# Master-Module.net
KiCad netlist of a schematic drawn in EAGLE
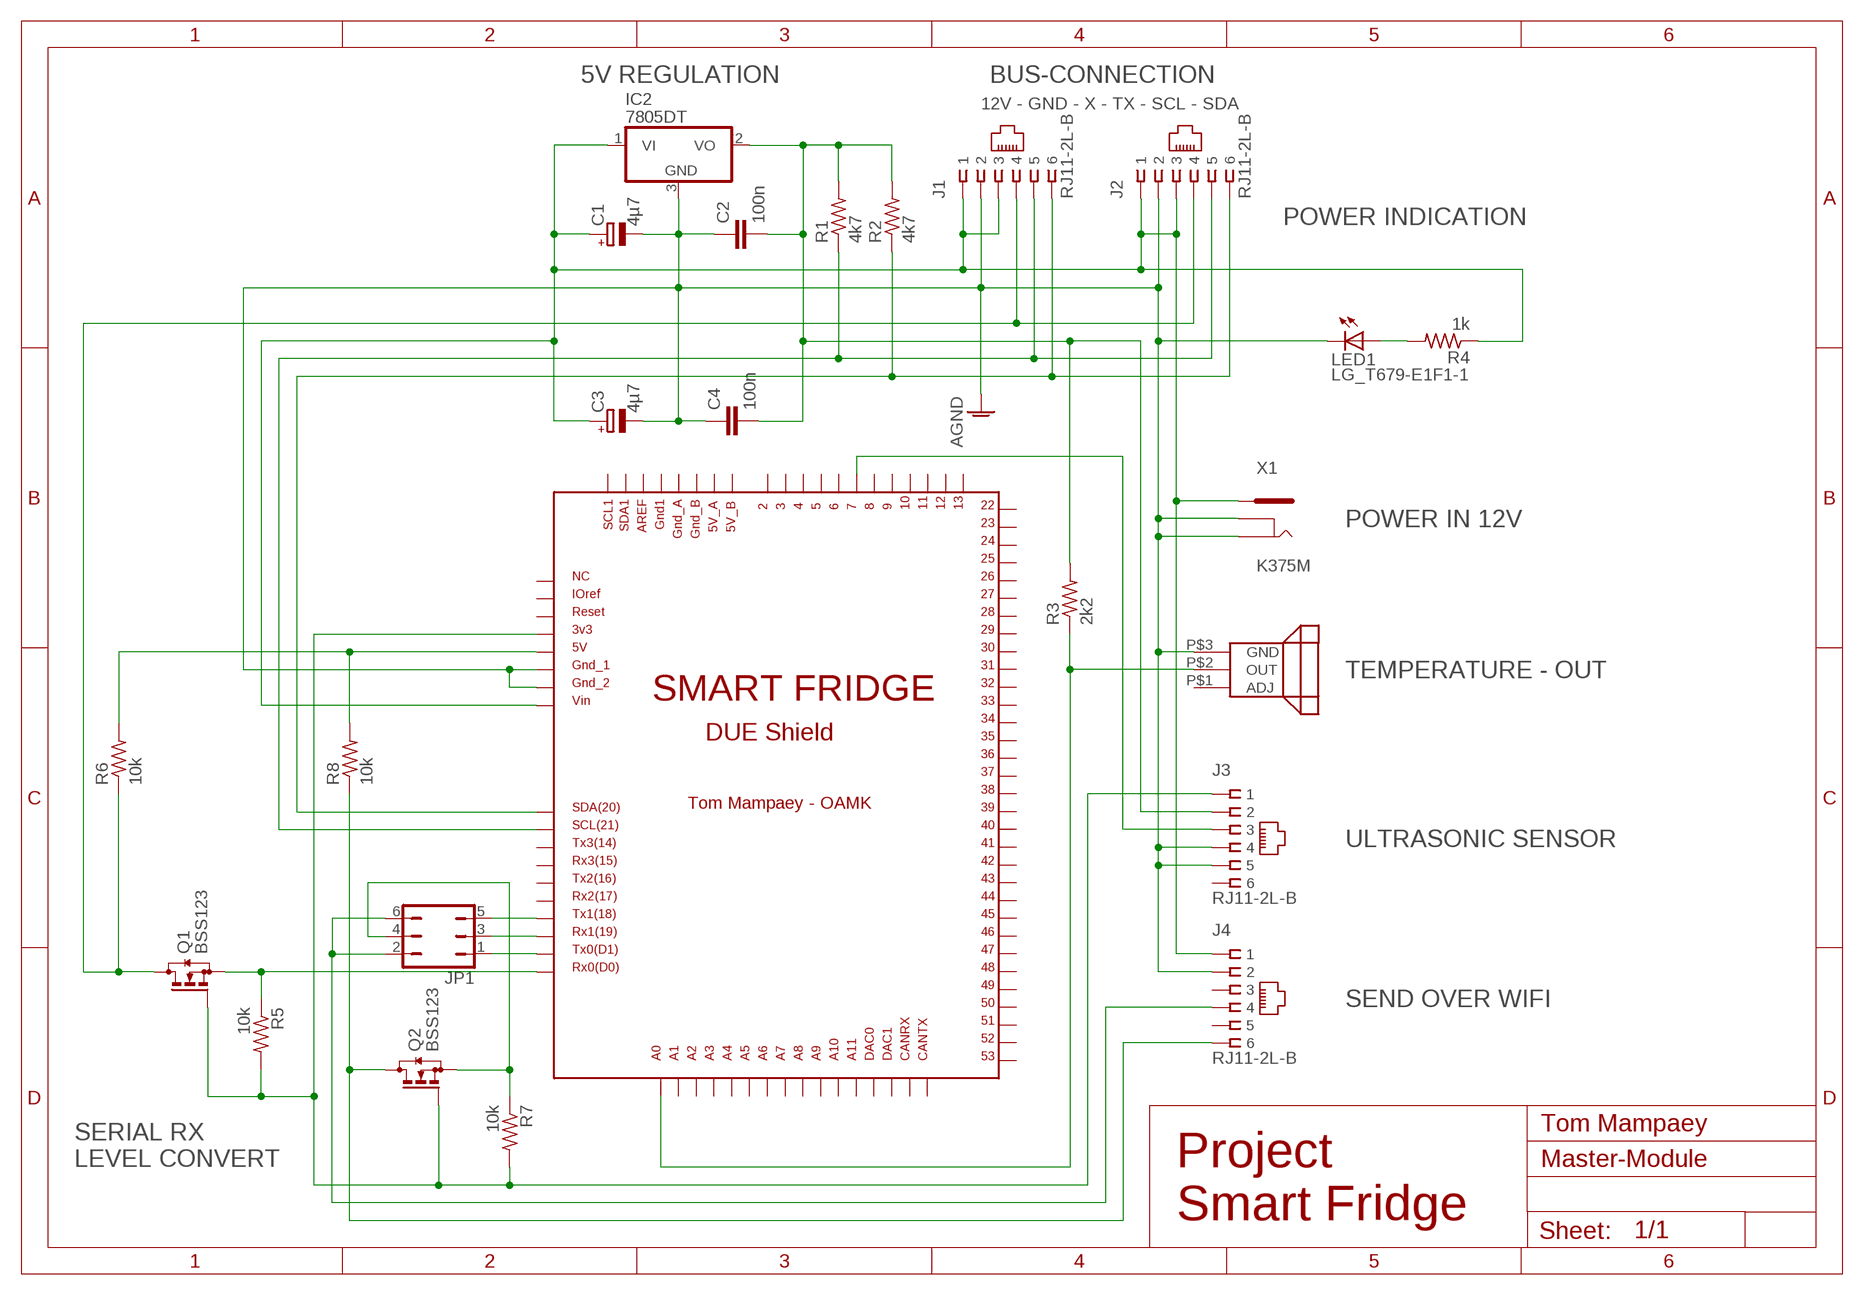
[diagram p0: schematic, sheet 1]

(export (version "E")
  (design (tool "Eeschema 10.0.6"))
  (components
    (comp (ref "C1")
      (value "4µ7")
      (footprint "eagle-import:PANASONIC_B")
      (libsource (lib "eagle-import") (part "CPOL-EUB"))
    )
    (comp (ref "C2")
      (value "100n")
      (footprint "eagle-import:C0603")
      (libsource (lib "eagle-import") (part "C-EUC0603"))
    )
    (comp (ref "C3")
      (value "4µ7")
      (footprint "eagle-import:PANASONIC_B")
      (libsource (lib "eagle-import") (part "CPOL-EUB"))
    )
    (comp (ref "C4")
      (value "100n")
      (footprint "eagle-import:C0603")
      (libsource (lib "eagle-import") (part "C-EUC0603"))
    )
    (comp (ref "IC2")
      (value "7805DT")
      (footprint "eagle-import:TO252")
      (libsource (lib "eagle-import") (part "78DT05"))
    )
    (comp (ref "J1")
      (value "RJ11-2L-B")
      (footprint "eagle-import:RJ11-NO_SHIELD")
      (fields (field (name "MF") "TYCO ELECTRONICS"))
      (libsource (lib "eagle-import") (part "RJ11-2L-B"))
    )
    (comp (ref "J2")
      (value "RJ11-2L-B")
      (footprint "eagle-import:RJ11-NO_SHIELD")
      (fields (field (name "MF") "TYCO ELECTRONICS"))
      (libsource (lib "eagle-import") (part "RJ11-2L-B"))
    )
    (comp (ref "J3")
      (value "RJ11-2L-B")
      (footprint "eagle-import:RJ11-NO_SHIELD")
      (fields (field (name "MF") "TYCO ELECTRONICS"))
      (libsource (lib "eagle-import") (part "RJ11-2L-B"))
    )
    (comp (ref "J4")
      (value "RJ11-2L-B")
      (footprint "eagle-import:RJ11-NO_SHIELD")
      (fields
        (field (name "MF") "TYCO ELECTRONICS")
        (field (name "MF_1") "TYCO ELECTRONICS")
        (field (name "MPN") "RJ11-2L-B")
        (field (name "OC_FARNELL") "unknown")
        (field (name "OC_NEWARK") "83F4463")
      )
      (libsource (lib "eagle-import") (part "RJ11-2L-B"))
    )
    (comp (ref "JP1")
      (value "JP3Q")
      (footprint "eagle-import:JP3Q")
      (libsource (lib "eagle-import") (part "JP3Q"))
    )
    (comp (ref "LED1")
      (value "LG_T679-E1F1-1")
      (footprint "eagle-import:PLCC2")
      (libsource (lib "eagle-import") (part "_T679-?-1E1F1LG"))
    )
    (comp (ref "Q1")
      (value "BSS123")
      (footprint "eagle-import:SOT23")
      (libsource (lib "eagle-import") (part "BSS123"))
    )
    (comp (ref "Q2")
      (value "BSS123")
      (footprint "eagle-import:SOT23")
      (libsource (lib "eagle-import") (part "BSS123"))
    )
    (comp (ref "R1")
      (value "4k7")
      (footprint "eagle-import:R0402")
      (libsource (lib "eagle-import") (part "R-US_R0402"))
    )
    (comp (ref "R2")
      (value "4k7")
      (footprint "eagle-import:R0402")
      (libsource (lib "eagle-import") (part "R-US_R0402"))
    )
    (comp (ref "R3")
      (value "2k2")
      (footprint "eagle-import:R0402")
      (libsource (lib "eagle-import") (part "R-US_R0402"))
    )
    (comp (ref "R4")
      (value "1k")
      (footprint "eagle-import:R0402")
      (libsource (lib "eagle-import") (part "R-US_R0402"))
    )
    (comp (ref "R5")
      (value "10k")
      (footprint "eagle-import:R0402")
      (libsource (lib "eagle-import") (part "R-US_R0402"))
    )
    (comp (ref "R6")
      (value "10k")
      (footprint "eagle-import:R0402")
      (libsource (lib "eagle-import") (part "R-US_R0402"))
    )
    (comp (ref "R7")
      (value "10k")
      (footprint "eagle-import:R0402")
      (libsource (lib "eagle-import") (part "R-US_R0402"))
    )
    (comp (ref "R8")
      (value "10k")
      (footprint "eagle-import:R0402")
      (libsource (lib "eagle-import") (part "R-US_R0402"))
    )
    (comp (ref "U$1")
      (value "DUE(NORMAL)")
      (footprint "eagle-import:DUE(NORMAL)")
      (libsource (lib "eagle-import") (part "DUE(NORMAL)"))
    )
    (comp (ref "U$2")
      (value "LM335")
      (footprint "eagle-import:LM335")
      (libsource (lib "eagle-import") (part "LM335"))
    )
    (comp (ref "X1")
      (value "K375M")
      (footprint "eagle-import:K375M")
      (libsource (lib "eagle-import") (part "K375M"))
    )
  )
  (nets
    (net (code "1") (name "AGND") (class "Default")
      (node (ref "C1") (pin "-") (pinfunction "-_-") (pintype "passive"))
      (node (ref "C2") (pin "1") (pinfunction "1_1") (pintype "passive"))
      (node (ref "C3") (pin "-") (pinfunction "-_-") (pintype "passive"))
      (node (ref "C4") (pin "1") (pinfunction "1_1") (pintype "passive"))
      (node (ref "IC2") (pin "3") (pinfunction "GND_3") (pintype "passive"))
      (node (ref "J1") (pin "2") (pinfunction "2_2") (pintype "passive"))
      (node (ref "J2") (pin "2") (pinfunction "2_2") (pintype "passive"))
      (node (ref "J3") (pin "4") (pinfunction "4_4") (pintype "passive"))
      (node (ref "J3") (pin "5") (pinfunction "5_5") (pintype "passive"))
      (node (ref "J4") (pin "2") (pinfunction "2_2") (pintype "passive"))
      (node (ref "LED1") (pin "C") (pinfunction "C_C") (pintype "passive"))
      (node (ref "U$1") (pin "GND_1") (pinfunction "GND_1_GND_1") (pintype "bidirectional"))
      (node (ref "U$1") (pin "GND_2") (pinfunction "GND_2_GND_2") (pintype "bidirectional"))
      (node (ref "U$2") (pin "P$3") (pinfunction "GND_P$3") (pintype "bidirectional"))
      (node (ref "X1") (pin "P$1") (pinfunction "2_P$1") (pintype "passive"))
      (node (ref "X1") (pin "P$6") (pinfunction "3_P$6") (pintype "passive"))
    )
    (net (code "2") (name "Net-(IC2-VI)") (class "Default")
      (node (ref "C1") (pin "+") (pinfunction "+_+") (pintype "passive"))
      (node (ref "C3") (pin "+") (pinfunction "+_+") (pintype "passive"))
      (node (ref "IC2") (pin "1") (pinfunction "VI_1") (pintype "input"))
      (node (ref "J1") (pin "1") (pinfunction "1_1") (pintype "passive"))
      (node (ref "J1") (pin "3") (pinfunction "3_3") (pintype "passive"))
      (node (ref "J2") (pin "1") (pinfunction "1_1") (pintype "passive"))
      (node (ref "J2") (pin "3") (pinfunction "3_3") (pintype "passive"))
      (node (ref "J4") (pin "1") (pinfunction "1_1") (pintype "passive"))
      (node (ref "R4") (pin "1") (pinfunction "1_1") (pintype "passive"))
      (node (ref "U$1") (pin "VIN") (pinfunction "VIN_VIN") (pintype "bidirectional"))
      (node (ref "X1") (pin "P$7") (pinfunction "1_P$7") (pintype "passive"))
    )
    (net (code "3") (name "Net-(IC2-VO)") (class "Default")
      (node (ref "C2") (pin "2") (pinfunction "2_2") (pintype "passive"))
      (node (ref "C4") (pin "2") (pinfunction "2_2") (pintype "passive"))
      (node (ref "IC2") (pin "2") (pinfunction "VO_2") (pintype "passive"))
      (node (ref "J3") (pin "2") (pinfunction "2_2") (pintype "passive"))
      (node (ref "R1") (pin "2") (pinfunction "2_2") (pintype "passive"))
      (node (ref "R2") (pin "2") (pinfunction "2_2") (pintype "passive"))
      (node (ref "R3") (pin "2") (pinfunction "2_2") (pintype "passive"))
    )
    (net (code "4") (name "Net-(J1-Pad5)") (class "Default")
      (node (ref "J1") (pin "5") (pinfunction "5_5") (pintype "passive"))
      (node (ref "J2") (pin "5") (pinfunction "5_5") (pintype "passive"))
      (node (ref "R1") (pin "1") (pinfunction "1_1") (pintype "passive"))
      (node (ref "U$1") (pin "SCL") (pinfunction "SCL_SCL") (pintype "bidirectional"))
    )
    (net (code "5") (name "Net-(J1-Pad6)") (class "Default")
      (node (ref "J1") (pin "6") (pinfunction "6_6") (pintype "passive"))
      (node (ref "J2") (pin "6") (pinfunction "6_6") (pintype "passive"))
      (node (ref "R2") (pin "1") (pinfunction "1_1") (pintype "passive"))
      (node (ref "U$1") (pin "SDA") (pinfunction "SDA_SDA") (pintype "bidirectional"))
    )
    (net (code "6") (name "Net-(J3-Pad3)") (class "Default")
      (node (ref "J3") (pin "3") (pinfunction "3_3") (pintype "passive"))
      (node (ref "U$1") (pin "7") (pinfunction "7_7") (pintype "bidirectional"))
    )
    (net (code "7") (name "Net-(J4-Pad4)") (class "Default")
      (node (ref "J4") (pin "4") (pinfunction "4_4") (pintype "passive"))
      (node (ref "JP1") (pin "2") (pinfunction "2_2") (pintype "passive"))
      (node (ref "JP1") (pin "6") (pinfunction "6_6") (pintype "passive"))
    )
    (net (code "8") (name "Net-(JP1-Pad1)") (class "Default")
      (node (ref "JP1") (pin "1") (pinfunction "1_1") (pintype "passive"))
      (node (ref "U$1") (pin "TX0") (pinfunction "TX0_TX0") (pintype "bidirectional"))
    )
    (net (code "9") (name "Net-(JP1-Pad3)") (class "Default")
      (node (ref "JP1") (pin "3") (pinfunction "3_3") (pintype "passive"))
      (node (ref "U$1") (pin "RX1") (pinfunction "RX1_RX1") (pintype "bidirectional"))
    )
    (net (code "10") (name "Net-(JP1-Pad5)") (class "Default")
      (node (ref "JP1") (pin "5") (pinfunction "5_5") (pintype "passive"))
      (node (ref "U$1") (pin "TX1") (pinfunction "TX1_TX1") (pintype "bidirectional"))
    )
    (net (code "11") (name "Net-(LED1-PadA)") (class "Default")
      (node (ref "LED1") (pin "A") (pinfunction "A_A") (pintype "passive"))
      (node (ref "R4") (pin "2") (pinfunction "2_2") (pintype "passive"))
    )
    (net (code "12") (name "Net-(Q1-D)") (class "Default")
      (node (ref "J1") (pin "4") (pinfunction "4_4") (pintype "passive"))
      (node (ref "J2") (pin "4") (pinfunction "4_4") (pintype "passive"))
      (node (ref "Q1") (pin "3") (pinfunction "D_3") (pintype "passive"))
      (node (ref "R6") (pin "1") (pinfunction "1_1") (pintype "passive"))
    )
    (net (code "13") (name "Net-(Q1-G)") (class "Default")
      (node (ref "J3") (pin "1") (pinfunction "1_1") (pintype "passive"))
      (node (ref "Q1") (pin "1") (pinfunction "G_1") (pintype "passive"))
      (node (ref "Q2") (pin "1") (pinfunction "G_1") (pintype "passive"))
      (node (ref "R5") (pin "2") (pinfunction "2_2") (pintype "passive"))
      (node (ref "R7") (pin "2") (pinfunction "2_2") (pintype "passive"))
      (node (ref "U$1") (pin "3V3") (pinfunction "3V3_3V3") (pintype "bidirectional"))
    )
    (net (code "14") (name "Net-(Q1-S)") (class "Default")
      (node (ref "Q1") (pin "2") (pinfunction "S_2") (pintype "passive"))
      (node (ref "R5") (pin "1") (pinfunction "1_1") (pintype "passive"))
      (node (ref "U$1") (pin "RX0") (pinfunction "RX0_RX0") (pintype "bidirectional"))
    )
    (net (code "15") (name "Net-(Q2-D)") (class "Default")
      (node (ref "J4") (pin "6") (pinfunction "6_6") (pintype "passive"))
      (node (ref "Q2") (pin "3") (pinfunction "D_3") (pintype "passive"))
      (node (ref "R8") (pin "1") (pinfunction "1_1") (pintype "passive"))
    )
    (net (code "16") (name "Net-(Q2-S)") (class "Default")
      (node (ref "JP1") (pin "4") (pinfunction "4_4") (pintype "passive"))
      (node (ref "Q2") (pin "2") (pinfunction "S_2") (pintype "passive"))
      (node (ref "R7") (pin "1") (pinfunction "1_1") (pintype "passive"))
    )
    (net (code "17") (name "Net-(R6-Pad2)") (class "Default")
      (node (ref "R6") (pin "2") (pinfunction "2_2") (pintype "passive"))
      (node (ref "R8") (pin "2") (pinfunction "2_2") (pintype "passive"))
      (node (ref "U$1") (pin "5V") (pinfunction "5V_5V") (pintype "bidirectional"))
    )
    (net (code "18") (name "Net-(U$2-OUT)") (class "Default")
      (node (ref "R3") (pin "1") (pinfunction "1_1") (pintype "passive"))
      (node (ref "U$1") (pin "A0") (pinfunction "A0_A0") (pintype "bidirectional"))
      (node (ref "U$2") (pin "P$2") (pinfunction "OUT_P$2") (pintype "bidirectional"))
    )
    (net (code "19") (name "unconnected-(J3-Pad6)") (class "Default")
      (node (ref "J3") (pin "6") (pinfunction "6_6") (pintype "passive"))
    )
    (net (code "20") (name "unconnected-(J4-Pad3)") (class "Default")
      (node (ref "J4") (pin "3") (pinfunction "3_3") (pintype "passive"))
    )
    (net (code "21") (name "unconnected-(J4-Pad5)") (class "Default")
      (node (ref "J4") (pin "5") (pinfunction "5_5") (pintype "passive"))
    )
    (net (code "22") (name "unconnected-(U$1-Pad2)") (class "Default")
      (node (ref "U$1") (pin "2") (pinfunction "2_2") (pintype "bidirectional"))
    )
    (net (code "23") (name "unconnected-(U$1-Pad3)") (class "Default")
      (node (ref "U$1") (pin "3") (pinfunction "3_3") (pintype "bidirectional"))
    )
    (net (code "24") (name "unconnected-(U$1-Pad4)") (class "Default")
      (node (ref "U$1") (pin "4") (pinfunction "4_4") (pintype "bidirectional"))
    )
    (net (code "25") (name "unconnected-(U$1-Pad5)") (class "Default")
      (node (ref "U$1") (pin "5") (pinfunction "5_5") (pintype "bidirectional"))
    )
    (net (code "26") (name "unconnected-(U$1-Pad5V_A)") (class "Default")
      (node (ref "U$1") (pin "5V_A") (pinfunction "5V_A_5V_A") (pintype "bidirectional"))
    )
    (net (code "27") (name "unconnected-(U$1-Pad5V_B)") (class "Default")
      (node (ref "U$1") (pin "5V_B") (pinfunction "5V_B_5V_B") (pintype "bidirectional"))
    )
    (net (code "28") (name "unconnected-(U$1-Pad6)") (class "Default")
      (node (ref "U$1") (pin "6") (pinfunction "6_6") (pintype "bidirectional"))
    )
    (net (code "29") (name "unconnected-(U$1-Pad8)") (class "Default")
      (node (ref "U$1") (pin "8") (pinfunction "8_8") (pintype "bidirectional"))
    )
    (net (code "30") (name "unconnected-(U$1-Pad9)") (class "Default")
      (node (ref "U$1") (pin "9") (pinfunction "9_9") (pintype "bidirectional"))
    )
    (net (code "31") (name "unconnected-(U$1-Pad10)") (class "Default")
      (node (ref "U$1") (pin "10") (pinfunction "10_10") (pintype "bidirectional"))
    )
    (net (code "32") (name "unconnected-(U$1-Pad11)") (class "Default")
      (node (ref "U$1") (pin "11") (pinfunction "11_11") (pintype "bidirectional"))
    )
    (net (code "33") (name "unconnected-(U$1-Pad12)") (class "Default")
      (node (ref "U$1") (pin "12") (pinfunction "12_12") (pintype "bidirectional"))
    )
    (net (code "34") (name "unconnected-(U$1-Pad13)") (class "Default")
      (node (ref "U$1") (pin "13") (pinfunction "13_13") (pintype "bidirectional"))
    )
    (net (code "35") (name "unconnected-(U$1-Pad22)") (class "Default")
      (node (ref "U$1") (pin "22") (pinfunction "22_22") (pintype "bidirectional"))
    )
    (net (code "36") (name "unconnected-(U$1-Pad23)") (class "Default")
      (node (ref "U$1") (pin "23") (pinfunction "23_23") (pintype "bidirectional"))
    )
    (net (code "37") (name "unconnected-(U$1-Pad24)") (class "Default")
      (node (ref "U$1") (pin "24") (pinfunction "24_24") (pintype "bidirectional"))
    )
    (net (code "38") (name "unconnected-(U$1-Pad25)") (class "Default")
      (node (ref "U$1") (pin "25") (pinfunction "25_25") (pintype "bidirectional"))
    )
    (net (code "39") (name "unconnected-(U$1-Pad26)") (class "Default")
      (node (ref "U$1") (pin "26") (pinfunction "26_26") (pintype "bidirectional"))
    )
    (net (code "40") (name "unconnected-(U$1-Pad27)") (class "Default")
      (node (ref "U$1") (pin "27") (pinfunction "27_27") (pintype "bidirectional"))
    )
    (net (code "41") (name "unconnected-(U$1-Pad28)") (class "Default")
      (node (ref "U$1") (pin "28") (pinfunction "28_28") (pintype "bidirectional"))
    )
    (net (code "42") (name "unconnected-(U$1-Pad29)") (class "Default")
      (node (ref "U$1") (pin "29") (pinfunction "29_29") (pintype "bidirectional"))
    )
    (net (code "43") (name "unconnected-(U$1-Pad30)") (class "Default")
      (node (ref "U$1") (pin "30") (pinfunction "30_30") (pintype "bidirectional"))
    )
    (net (code "44") (name "unconnected-(U$1-Pad31)") (class "Default")
      (node (ref "U$1") (pin "31") (pinfunction "31_31") (pintype "bidirectional"))
    )
    (net (code "45") (name "unconnected-(U$1-Pad32)") (class "Default")
      (node (ref "U$1") (pin "32") (pinfunction "32_32") (pintype "bidirectional"))
    )
    (net (code "46") (name "unconnected-(U$1-Pad33)") (class "Default")
      (node (ref "U$1") (pin "33") (pinfunction "33_33") (pintype "bidirectional"))
    )
    (net (code "47") (name "unconnected-(U$1-Pad34)") (class "Default")
      (node (ref "U$1") (pin "34") (pinfunction "34_34") (pintype "bidirectional"))
    )
    (net (code "48") (name "unconnected-(U$1-Pad35)") (class "Default")
      (node (ref "U$1") (pin "35") (pinfunction "35_35") (pintype "bidirectional"))
    )
    (net (code "49") (name "unconnected-(U$1-Pad36)") (class "Default")
      (node (ref "U$1") (pin "36") (pinfunction "36_36") (pintype "bidirectional"))
    )
    (net (code "50") (name "unconnected-(U$1-Pad37)") (class "Default")
      (node (ref "U$1") (pin "37") (pinfunction "37_37") (pintype "bidirectional"))
    )
    (net (code "51") (name "unconnected-(U$1-Pad38)") (class "Default")
      (node (ref "U$1") (pin "38") (pinfunction "38_38") (pintype "bidirectional"))
    )
    (net (code "52") (name "unconnected-(U$1-Pad39)") (class "Default")
      (node (ref "U$1") (pin "39") (pinfunction "39_39") (pintype "bidirectional"))
    )
    (net (code "53") (name "unconnected-(U$1-Pad40)") (class "Default")
      (node (ref "U$1") (pin "40") (pinfunction "40_40") (pintype "bidirectional"))
    )
    (net (code "54") (name "unconnected-(U$1-Pad41)") (class "Default")
      (node (ref "U$1") (pin "41") (pinfunction "41_41") (pintype "bidirectional"))
    )
    (net (code "55") (name "unconnected-(U$1-Pad42)") (class "Default")
      (node (ref "U$1") (pin "42") (pinfunction "42_42") (pintype "bidirectional"))
    )
    (net (code "56") (name "unconnected-(U$1-Pad43)") (class "Default")
      (node (ref "U$1") (pin "43") (pinfunction "43_43") (pintype "bidirectional"))
    )
    (net (code "57") (name "unconnected-(U$1-Pad44)") (class "Default")
      (node (ref "U$1") (pin "44") (pinfunction "44_44") (pintype "bidirectional"))
    )
    (net (code "58") (name "unconnected-(U$1-Pad45)") (class "Default")
      (node (ref "U$1") (pin "45") (pinfunction "45_45") (pintype "bidirectional"))
    )
    (net (code "59") (name "unconnected-(U$1-Pad46)") (class "Default")
      (node (ref "U$1") (pin "46") (pinfunction "46_46") (pintype "bidirectional"))
    )
    (net (code "60") (name "unconnected-(U$1-Pad47)") (class "Default")
      (node (ref "U$1") (pin "47") (pinfunction "47_47") (pintype "bidirectional"))
    )
    (net (code "61") (name "unconnected-(U$1-Pad48)") (class "Default")
      (node (ref "U$1") (pin "48") (pinfunction "48_48") (pintype "bidirectional"))
    )
    (net (code "62") (name "unconnected-(U$1-Pad49)") (class "Default")
      (node (ref "U$1") (pin "49") (pinfunction "49_49") (pintype "bidirectional"))
    )
    (net (code "63") (name "unconnected-(U$1-Pad50)") (class "Default")
      (node (ref "U$1") (pin "50") (pinfunction "50_50") (pintype "bidirectional"))
    )
    (net (code "64") (name "unconnected-(U$1-Pad51)") (class "Default")
      (node (ref "U$1") (pin "51") (pinfunction "51_51") (pintype "bidirectional"))
    )
    (net (code "65") (name "unconnected-(U$1-Pad52)") (class "Default")
      (node (ref "U$1") (pin "52") (pinfunction "52_52") (pintype "bidirectional"))
    )
    (net (code "66") (name "unconnected-(U$1-Pad53)") (class "Default")
      (node (ref "U$1") (pin "53") (pinfunction "53_53") (pintype "bidirectional"))
    )
    (net (code "67") (name "unconnected-(U$1-PadA1)") (class "Default")
      (node (ref "U$1") (pin "A1") (pinfunction "A1_A1") (pintype "bidirectional"))
    )
    (net (code "68") (name "unconnected-(U$1-PadA2)") (class "Default")
      (node (ref "U$1") (pin "A2") (pinfunction "A2_A2") (pintype "bidirectional"))
    )
    (net (code "69") (name "unconnected-(U$1-PadA3)") (class "Default")
      (node (ref "U$1") (pin "A3") (pinfunction "A3_A3") (pintype "bidirectional"))
    )
    (net (code "70") (name "unconnected-(U$1-PadA4)") (class "Default")
      (node (ref "U$1") (pin "A4") (pinfunction "A4_A4") (pintype "bidirectional"))
    )
    (net (code "71") (name "unconnected-(U$1-PadA5)") (class "Default")
      (node (ref "U$1") (pin "A5") (pinfunction "A5_A5") (pintype "bidirectional"))
    )
    (net (code "72") (name "unconnected-(U$1-PadA6)") (class "Default")
      (node (ref "U$1") (pin "A6") (pinfunction "A6_A6") (pintype "bidirectional"))
    )
    (net (code "73") (name "unconnected-(U$1-PadA7)") (class "Default")
      (node (ref "U$1") (pin "A7") (pinfunction "A7_A7") (pintype "bidirectional"))
    )
    (net (code "74") (name "unconnected-(U$1-PadA8)") (class "Default")
      (node (ref "U$1") (pin "A8") (pinfunction "A8_A8") (pintype "bidirectional"))
    )
    (net (code "75") (name "unconnected-(U$1-PadA9)") (class "Default")
      (node (ref "U$1") (pin "A9") (pinfunction "A9_A9") (pintype "bidirectional"))
    )
    (net (code "76") (name "unconnected-(U$1-PadA10)") (class "Default")
      (node (ref "U$1") (pin "A10") (pinfunction "A10_A10") (pintype "bidirectional"))
    )
    (net (code "77") (name "unconnected-(U$1-PadA11)") (class "Default")
      (node (ref "U$1") (pin "A11") (pinfunction "A11_A11") (pintype "bidirectional"))
    )
    (net (code "78") (name "unconnected-(U$1-PadAREF)") (class "Default")
      (node (ref "U$1") (pin "AREF") (pinfunction "AREF_AREF") (pintype "bidirectional"))
    )
    (net (code "79") (name "unconnected-(U$1-PadCANRX)") (class "Default")
      (node (ref "U$1") (pin "CANRX") (pinfunction "CANRX_CANRX") (pintype "bidirectional"))
    )
    (net (code "80") (name "unconnected-(U$1-PadCANTX)") (class "Default")
      (node (ref "U$1") (pin "CANTX") (pinfunction "CANTX_CANTX") (pintype "bidirectional"))
    )
    (net (code "81") (name "unconnected-(U$1-PadDAC0)") (class "Default")
      (node (ref "U$1") (pin "DAC0") (pinfunction "DAC0_DAC0") (pintype "bidirectional"))
    )
    (net (code "82") (name "unconnected-(U$1-PadDAC1)") (class "Default")
      (node (ref "U$1") (pin "DAC1") (pinfunction "DAC1_DAC1") (pintype "bidirectional"))
    )
    (net (code "83") (name "unconnected-(U$1-PadGND1)") (class "Default")
      (node (ref "U$1") (pin "GND1") (pinfunction "GND1_GND1") (pintype "bidirectional"))
    )
    (net (code "84") (name "unconnected-(U$1-PadGND_A)") (class "Default")
      (node (ref "U$1") (pin "GND_A") (pinfunction "GND_A_GND_A") (pintype "bidirectional"))
    )
    (net (code "85") (name "unconnected-(U$1-PadGND_B)") (class "Default")
      (node (ref "U$1") (pin "GND_B") (pinfunction "GND_B_GND_B") (pintype "bidirectional"))
    )
    (net (code "86") (name "unconnected-(U$1-PadIOREF)") (class "Default")
      (node (ref "U$1") (pin "IOREF") (pinfunction "IOREF_IOREF") (pintype "bidirectional"))
    )
    (net (code "87") (name "unconnected-(U$1-PadNC)") (class "Default")
      (node (ref "U$1") (pin "NC") (pinfunction "NC_NC") (pintype "bidirectional"))
    )
    (net (code "88") (name "unconnected-(U$1-PadRESET)") (class "Default")
      (node (ref "U$1") (pin "RESET") (pinfunction "RESET_RESET") (pintype "bidirectional"))
    )
    (net (code "89") (name "unconnected-(U$1-PadRX2)") (class "Default")
      (node (ref "U$1") (pin "RX2") (pinfunction "RX2_RX2") (pintype "bidirectional"))
    )
    (net (code "90") (name "unconnected-(U$1-PadRX3)") (class "Default")
      (node (ref "U$1") (pin "RX3") (pinfunction "RX3_RX3") (pintype "bidirectional"))
    )
    (net (code "91") (name "unconnected-(U$1-PadSCL1)") (class "Default")
      (node (ref "U$1") (pin "SCL1") (pinfunction "SCL1_SCL1") (pintype "bidirectional"))
    )
    (net (code "92") (name "unconnected-(U$1-PadSDA1)") (class "Default")
      (node (ref "U$1") (pin "SDA1") (pinfunction "SDA1_SDA1") (pintype "bidirectional"))
    )
    (net (code "93") (name "unconnected-(U$1-PadTX2)") (class "Default")
      (node (ref "U$1") (pin "TX2") (pinfunction "TX2_TX2") (pintype "bidirectional"))
    )
    (net (code "94") (name "unconnected-(U$1-PadTX3)") (class "Default")
      (node (ref "U$1") (pin "TX3") (pinfunction "TX3_TX3") (pintype "bidirectional"))
    )
    (net (code "95") (name "unconnected-(U$2-ADJ-PadP$1)") (class "Default")
      (node (ref "U$2") (pin "P$1") (pinfunction "ADJ_P$1") (pintype "bidirectional"))
    )
  )
)
